# decouple_caps.net
KiCad netlist of a schematic drawn in Altium Designer
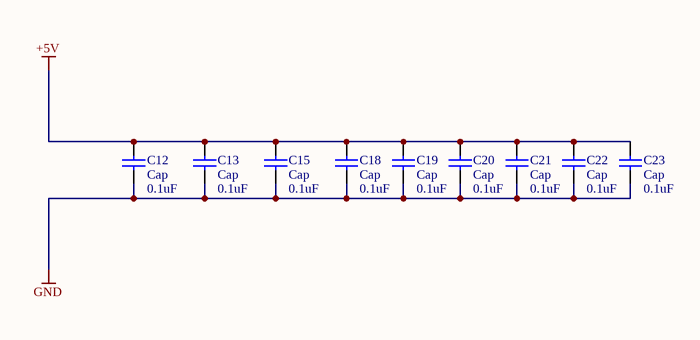
[diagram p0: decouple_caps.SchDoc]

(export (version "E")
  (design (tool "Eeschema 10.0.6"))
  (components
    (comp (ref "C12")
      (value "Cap")
      (footprint "C0805")
      (description "Capacitor")
      (fields (field (name "ALTIUM_VALUE") "0.1uF") (field (name "PUBLISHER") "Altium Limited"))
      (libsource (lib "Miscellaneous Devices") (part "Cap"))
    )
    (comp (ref "C13")
      (value "Cap")
      (footprint "C0805")
      (description "Capacitor")
      (fields (field (name "ALTIUM_VALUE") "0.1uF") (field (name "PUBLISHER") "Altium Limited"))
      (libsource (lib "Miscellaneous Devices") (part "Cap"))
    )
    (comp (ref "C15")
      (value "Cap")
      (footprint "C0805")
      (description "Capacitor")
      (fields (field (name "ALTIUM_VALUE") "0.1uF") (field (name "PUBLISHER") "Altium Limited"))
      (libsource (lib "Miscellaneous Devices") (part "Cap"))
    )
    (comp (ref "C18")
      (value "Cap")
      (footprint "C0805")
      (description "Capacitor")
      (fields (field (name "ALTIUM_VALUE") "0.1uF") (field (name "PUBLISHER") "Altium Limited"))
      (libsource (lib "Miscellaneous Devices") (part "Cap"))
    )
    (comp (ref "C19")
      (value "Cap")
      (footprint "C0805")
      (description "Capacitor")
      (fields (field (name "ALTIUM_VALUE") "0.1uF") (field (name "PUBLISHER") "Altium Limited"))
      (libsource (lib "Miscellaneous Devices") (part "Cap"))
    )
    (comp (ref "C20")
      (value "Cap")
      (footprint "C0805")
      (description "Capacitor")
      (fields (field (name "ALTIUM_VALUE") "0.1uF") (field (name "PUBLISHER") "Altium Limited"))
      (libsource (lib "Miscellaneous Devices") (part "Cap"))
    )
    (comp (ref "C21")
      (value "Cap")
      (footprint "C0805")
      (description "Capacitor")
      (fields (field (name "ALTIUM_VALUE") "0.1uF") (field (name "PUBLISHER") "Altium Limited"))
      (libsource (lib "Miscellaneous Devices") (part "Cap"))
    )
    (comp (ref "C22")
      (value "Cap")
      (footprint "C0805")
      (description "Capacitor")
      (fields (field (name "ALTIUM_VALUE") "0.1uF") (field (name "PUBLISHER") "Altium Limited"))
      (libsource (lib "Miscellaneous Devices") (part "Cap"))
    )
    (comp (ref "C23")
      (value "Cap")
      (footprint "C0805")
      (description "Capacitor")
      (fields (field (name "ALTIUM_VALUE") "0.1uF") (field (name "PUBLISHER") "Altium Limited"))
      (libsource (lib "Miscellaneous Devices") (part "Cap"))
    )
  )
  (nets
    (net (code "1") (name "+5V") (class "Default")
      (node (ref "C12") (pin "2") (pinfunction "2_2") (pintype "passive"))
      (node (ref "C13") (pin "2") (pinfunction "2_2") (pintype "passive"))
      (node (ref "C15") (pin "2") (pinfunction "2_2") (pintype "passive"))
      (node (ref "C18") (pin "2") (pinfunction "2_2") (pintype "passive"))
      (node (ref "C19") (pin "2") (pinfunction "2_2") (pintype "passive"))
      (node (ref "C20") (pin "2") (pinfunction "2_2") (pintype "passive"))
      (node (ref "C21") (pin "2") (pinfunction "2_2") (pintype "passive"))
      (node (ref "C22") (pin "2") (pinfunction "2_2") (pintype "passive"))
      (node (ref "C23") (pin "2") (pinfunction "2_2") (pintype "passive"))
    )
    (net (code "2") (name "GND") (class "Default")
      (node (ref "C12") (pin "1") (pinfunction "1_1") (pintype "passive"))
      (node (ref "C13") (pin "1") (pinfunction "1_1") (pintype "passive"))
      (node (ref "C15") (pin "1") (pinfunction "1_1") (pintype "passive"))
      (node (ref "C18") (pin "1") (pinfunction "1_1") (pintype "passive"))
      (node (ref "C19") (pin "1") (pinfunction "1_1") (pintype "passive"))
      (node (ref "C20") (pin "1") (pinfunction "1_1") (pintype "passive"))
      (node (ref "C21") (pin "1") (pinfunction "1_1") (pintype "passive"))
      (node (ref "C22") (pin "1") (pinfunction "1_1") (pintype "passive"))
      (node (ref "C23") (pin "1") (pinfunction "1_1") (pintype "passive"))
    )
  )
)
